# EMG-single.net
KiCad netlist of a schematic drawn in EAGLE
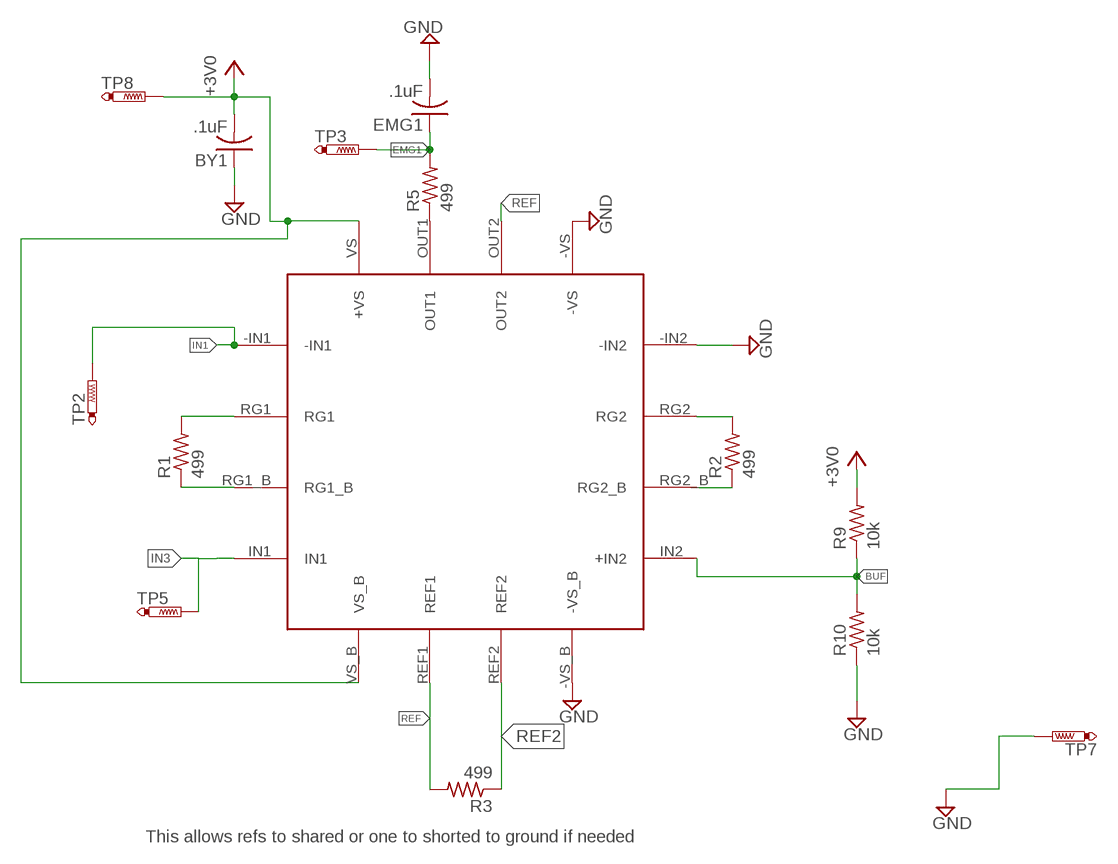
[diagram p0: schematic, sheet 1]

(export (version "E")
  (design (tool "Eeschema 10.0.6"))
  (components
    (comp (ref "BY1")
      (value ".1uF")
      (footprint "eagle-import:C0805")
      (libsource (lib "eagle-import") (part "C-USC0805"))
    )
    (comp (ref "EMG1")
      (value ".1uF")
      (footprint "eagle-import:C0805")
      (libsource (lib "eagle-import") (part "C-USC0805"))
    )
    (comp (ref "R1")
      (value "499")
      (footprint "eagle-import:R0805")
      (libsource (lib "eagle-import") (part "R-US_R0805"))
    )
    (comp (ref "R2")
      (value "499")
      (footprint "eagle-import:R0805")
      (libsource (lib "eagle-import") (part "R-US_R0805"))
    )
    (comp (ref "R3")
      (value "499")
      (footprint "eagle-import:R0805")
      (libsource (lib "eagle-import") (part "R-US_R0805"))
    )
    (comp (ref "R5")
      (value "499")
      (footprint "eagle-import:R0805")
      (libsource (lib "eagle-import") (part "R-US_R0805"))
    )
    (comp (ref "R9")
      (value "10k")
      (footprint "eagle-import:R0805")
      (libsource (lib "eagle-import") (part "R-US_R0805"))
    )
    (comp (ref "R10")
      (value "10k")
      (footprint "eagle-import:R0805")
      (libsource (lib "eagle-import") (part "R-US_R0805"))
    )
    (comp (ref "TP2")
      (value "PTR1TP20SQ")
      (footprint "eagle-import:TP20SQ")
      (libsource (lib "eagle-import") (part "PTR1TP20SQ"))
    )
    (comp (ref "TP3")
      (value "PTR1TP20SQ")
      (footprint "eagle-import:TP20SQ")
      (libsource (lib "eagle-import") (part "PTR1TP20SQ"))
    )
    (comp (ref "TP5")
      (value "PTR1TP20SQ")
      (footprint "eagle-import:TP20SQ")
      (libsource (lib "eagle-import") (part "PTR1TP20SQ"))
    )
    (comp (ref "TP7")
      (value "PTR1TP20SQ")
      (footprint "eagle-import:TP20SQ")
      (libsource (lib "eagle-import") (part "PTR1TP20SQ"))
    )
    (comp (ref "TP8")
      (value "PTR1TP20SQ")
      (footprint "eagle-import:TP20SQ")
      (libsource (lib "eagle-import") (part "PTR1TP20SQ"))
    )
    (comp (ref "U$9")
      (value "AD8222")
      (footprint "eagle-import:QFN-16")
      (libsource (lib "eagle-import") (part "AD8222"))
    )
  )
  (nets
    (net (code "1") (name "+3V0") (class "Default")
      (node (ref "BY1") (pin "2") (pinfunction "2_2") (pintype "passive"))
      (node (ref "R9") (pin "2") (pinfunction "2_2") (pintype "passive"))
      (node (ref "TP8") (pin "TP") (pinfunction "TP_TP") (pintype "input"))
      (node (ref "U$9") (pin "VS") (pinfunction "+VS_VS") (pintype "bidirectional"))
      (node (ref "U$9") (pin "VS_B") (pinfunction "VS_B_VS_B") (pintype "bidirectional"))
    )
    (net (code "2") (name "BUF") (class "Default")
      (node (ref "R10") (pin "2") (pinfunction "2_2") (pintype "passive"))
      (node (ref "R9") (pin "1") (pinfunction "1_1") (pintype "passive"))
      (node (ref "U$9") (pin "IN2") (pinfunction "+IN2_IN2") (pintype "bidirectional"))
    )
    (net (code "3") (name "EMG1") (class "Default")
      (node (ref "EMG1") (pin "1") (pinfunction "1_1") (pintype "passive"))
      (node (ref "R5") (pin "2") (pinfunction "2_2") (pintype "passive"))
      (node (ref "TP3") (pin "TP") (pinfunction "TP_TP") (pintype "input"))
    )
    (net (code "4") (name "GND") (class "Default")
      (node (ref "BY1") (pin "1") (pinfunction "1_1") (pintype "passive"))
      (node (ref "EMG1") (pin "2") (pinfunction "2_2") (pintype "passive"))
      (node (ref "R10") (pin "1") (pinfunction "1_1") (pintype "passive"))
      (node (ref "TP7") (pin "TP") (pinfunction "TP_TP") (pintype "input"))
      (node (ref "U$9") (pin "-IN2") (pinfunction "-IN2_-IN2") (pintype "bidirectional"))
      (node (ref "U$9") (pin "-VS") (pinfunction "-VS_-VS") (pintype "bidirectional"))
      (node (ref "U$9") (pin "-VS_B") (pinfunction "-VS_B_-VS_B") (pintype "bidirectional"))
    )
    (net (code "5") (name "IN1") (class "Default")
      (node (ref "TP2") (pin "TP") (pinfunction "TP_TP") (pintype "input"))
      (node (ref "U$9") (pin "-IN1") (pinfunction "-IN1_-IN1") (pintype "bidirectional"))
    )
    (net (code "6") (name "IN3") (class "Default")
      (node (ref "TP5") (pin "TP") (pinfunction "TP_TP") (pintype "input"))
      (node (ref "U$9") (pin "IN1") (pinfunction "IN1_IN1") (pintype "bidirectional"))
    )
    (net (code "7") (name "Net-(R1-Pad1)") (class "Default")
      (node (ref "R1") (pin "1") (pinfunction "1_1") (pintype "passive"))
      (node (ref "U$9") (pin "RG1_B") (pinfunction "RG1_B_RG1_B") (pintype "bidirectional"))
    )
    (net (code "8") (name "Net-(R1-Pad2)") (class "Default")
      (node (ref "R1") (pin "2") (pinfunction "2_2") (pintype "passive"))
      (node (ref "U$9") (pin "RG1") (pinfunction "RG1_RG1") (pintype "bidirectional"))
    )
    (net (code "9") (name "Net-(R2-Pad1)") (class "Default")
      (node (ref "R2") (pin "1") (pinfunction "1_1") (pintype "passive"))
      (node (ref "U$9") (pin "RG2_B") (pinfunction "RG2_B_RG2_B") (pintype "bidirectional"))
    )
    (net (code "10") (name "Net-(R2-Pad2)") (class "Default")
      (node (ref "R2") (pin "2") (pinfunction "2_2") (pintype "passive"))
      (node (ref "U$9") (pin "RG2") (pinfunction "RG2_RG2") (pintype "bidirectional"))
    )
    (net (code "11") (name "Net-(R5-Pad1)") (class "Default")
      (node (ref "R5") (pin "1") (pinfunction "1_1") (pintype "passive"))
      (node (ref "U$9") (pin "OUT1") (pinfunction "OUT1_OUT1") (pintype "bidirectional"))
    )
    (net (code "12") (name "REF") (class "Default")
      (node (ref "R3") (pin "2") (pinfunction "2_2") (pintype "passive"))
      (node (ref "U$9") (pin "OUT2") (pinfunction "OUT2_OUT2") (pintype "bidirectional"))
      (node (ref "U$9") (pin "REF1") (pinfunction "REF1_REF1") (pintype "bidirectional"))
    )
    (net (code "13") (name "REF2") (class "Default")
      (node (ref "R3") (pin "1") (pinfunction "1_1") (pintype "passive"))
      (node (ref "U$9") (pin "REF2") (pinfunction "REF2_REF2") (pintype "bidirectional"))
    )
  )
)
